# klt-j4k-ov2732.net
KiCad netlist of a schematic drawn in Altium Designer
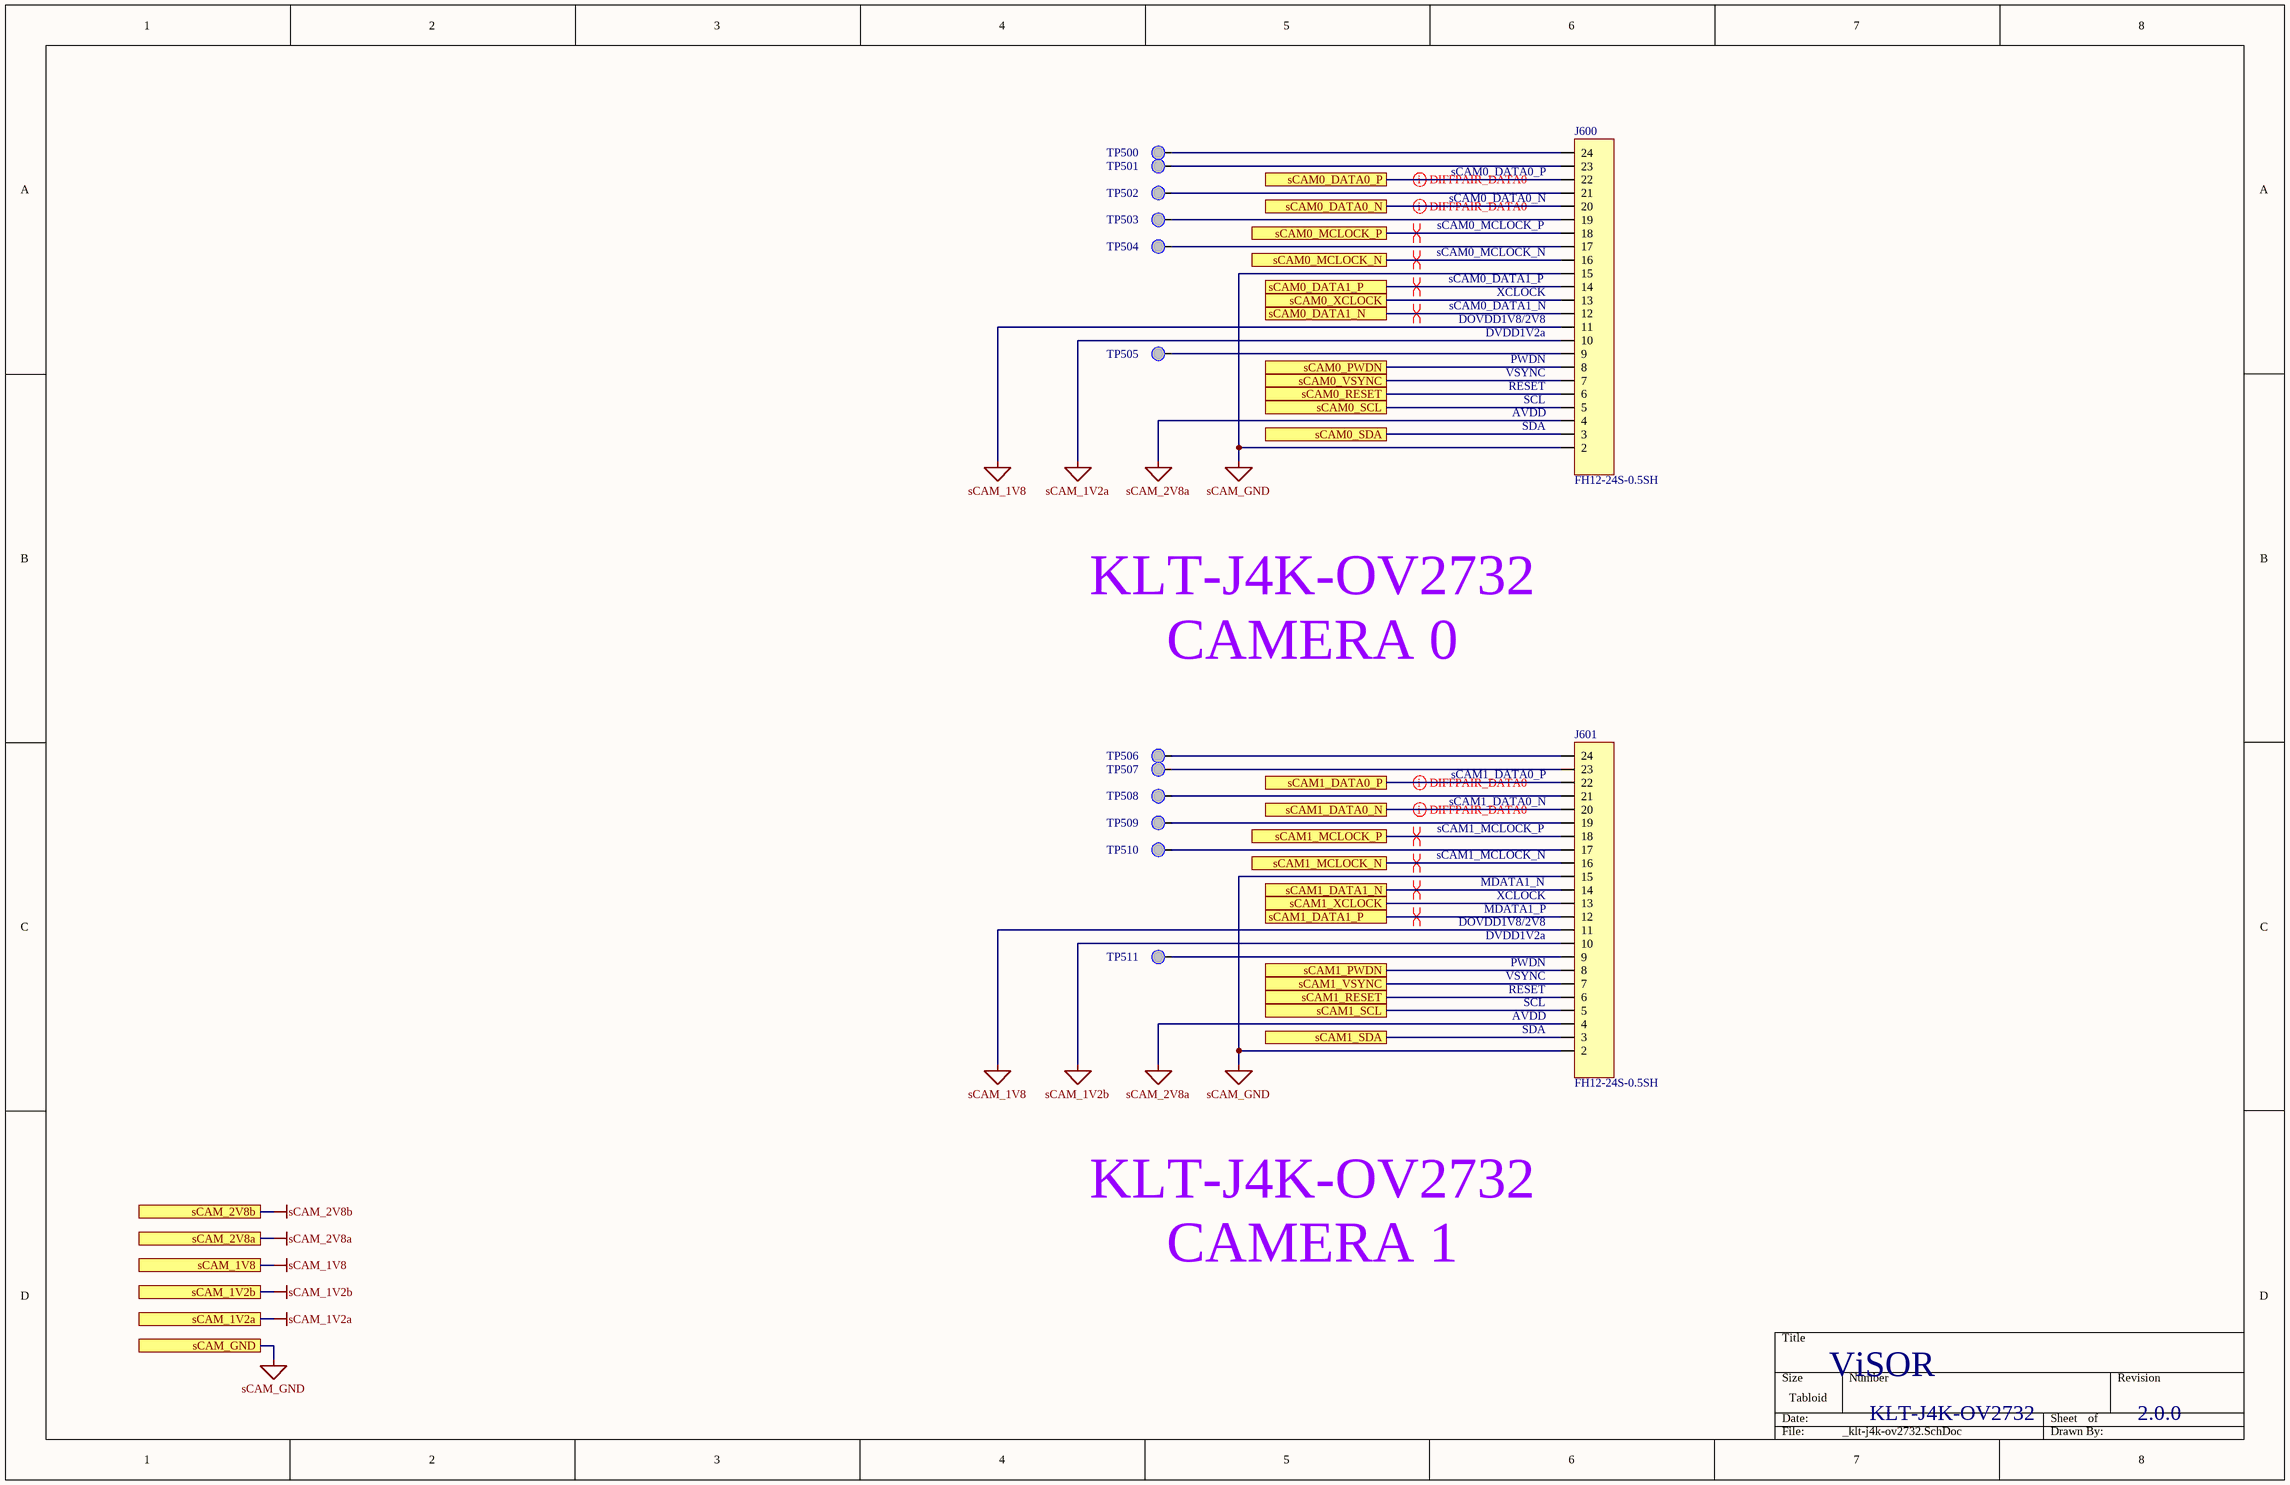
[diagram p0: _klt-j4k-ov2732.SchDoc]

(export (version "E")
  (design (tool "Eeschema 10.0.6"))
  (components
    (comp (ref "J600")
      (value "FH12-24S-0.5SH")
      (footprint "FH12-24S-0.5SH")
      (description "ONN FFC BOTTOM 24POS 0.50MM R/A")
      (libsource (lib "hirose") (part "FH12-24S-0.5SH"))
    )
    (comp (ref "J601")
      (value "FH12-24S-0.5SH")
      (footprint "FH12-24S-0.5SH")
      (description "ONN FFC BOTTOM 24POS 0.50MM R/A")
      (libsource (lib "hirose") (part "FH12-24S-0.5SH"))
    )
    (comp (ref "TP500") (value "TP") (footprint "TP_TH") (libsource (lib "common") (part "TP")))
    (comp (ref "TP501") (value "TP") (footprint "TP_TH") (libsource (lib "common") (part "TP")))
    (comp (ref "TP502") (value "TP") (footprint "TP_TH") (libsource (lib "common") (part "TP")))
    (comp (ref "TP503") (value "TP") (footprint "TP_TH") (libsource (lib "common") (part "TP")))
    (comp (ref "TP504") (value "TP") (footprint "TP_TH") (libsource (lib "common") (part "TP")))
    (comp (ref "TP505") (value "TP") (footprint "TP_TH") (libsource (lib "common") (part "TP")))
    (comp (ref "TP506") (value "TP") (footprint "TP_TH") (libsource (lib "common") (part "TP")))
    (comp (ref "TP507") (value "TP") (footprint "TP_TH") (libsource (lib "common") (part "TP")))
    (comp (ref "TP508") (value "TP") (footprint "TP_TH") (libsource (lib "common") (part "TP")))
    (comp (ref "TP509") (value "TP") (footprint "TP_TH") (libsource (lib "common") (part "TP")))
    (comp (ref "TP510") (value "TP") (footprint "TP_TH") (libsource (lib "common") (part "TP")))
    (comp (ref "TP511") (value "TP") (footprint "TP_TH") (libsource (lib "common") (part "TP")))
  )
  (nets
    (net (code "1") (name "/sCAM0_DATA0_N") (class "Default")
      (node (ref "J600") (pin "20") (pinfunction "20_20") (pintype "passive"))
    )
    (net (code "2") (name "/sCAM0_DATA0_P") (class "Default")
      (node (ref "J600") (pin "22") (pinfunction "22_22") (pintype "passive"))
    )
    (net (code "3") (name "/sCAM0_DATA1_N") (class "Default")
      (node (ref "J600") (pin "12") (pinfunction "12_12") (pintype "passive"))
    )
    (net (code "4") (name "/sCAM0_DATA1_P") (class "Default")
      (node (ref "J600") (pin "14") (pinfunction "14_14") (pintype "passive"))
    )
    (net (code "5") (name "/sCAM0_MCLOCK_N") (class "Default")
      (node (ref "J600") (pin "16") (pinfunction "16_16") (pintype "passive"))
    )
    (net (code "6") (name "/sCAM0_MCLOCK_P") (class "Default")
      (node (ref "J600") (pin "18") (pinfunction "18_18") (pintype "passive"))
    )
    (net (code "7") (name "/sCAM0_PWDN") (class "Default")
      (node (ref "J600") (pin "8") (pinfunction "8_8") (pintype "passive"))
    )
    (net (code "8") (name "/sCAM0_RESET") (class "Default")
      (node (ref "J600") (pin "6") (pinfunction "6_6") (pintype "passive"))
    )
    (net (code "9") (name "/sCAM0_SCL") (class "Default")
      (node (ref "J600") (pin "5") (pinfunction "5_5") (pintype "passive"))
    )
    (net (code "10") (name "/sCAM0_SDA") (class "Default")
      (node (ref "J600") (pin "3") (pinfunction "3_3") (pintype "passive"))
    )
    (net (code "11") (name "/sCAM0_VSYNC") (class "Default")
      (node (ref "J600") (pin "7") (pinfunction "7_7") (pintype "passive"))
    )
    (net (code "12") (name "/sCAM0_XCLOCK") (class "Default")
      (node (ref "J600") (pin "13") (pinfunction "13_13") (pintype "passive"))
    )
    (net (code "13") (name "/sCAM1_DATA0_N") (class "Default")
      (node (ref "J601") (pin "20") (pinfunction "20_20") (pintype "passive"))
    )
    (net (code "14") (name "/sCAM1_DATA0_P") (class "Default")
      (node (ref "J601") (pin "22") (pinfunction "22_22") (pintype "passive"))
    )
    (net (code "15") (name "/sCAM1_DATA1_N") (class "Default")
      (node (ref "J601") (pin "14") (pinfunction "14_14") (pintype "passive"))
    )
    (net (code "16") (name "/sCAM1_DATA1_P") (class "Default")
      (node (ref "J601") (pin "12") (pinfunction "12_12") (pintype "passive"))
    )
    (net (code "17") (name "/sCAM1_MCLOCK_N") (class "Default")
      (node (ref "J601") (pin "16") (pinfunction "16_16") (pintype "passive"))
    )
    (net (code "18") (name "/sCAM1_MCLOCK_P") (class "Default")
      (node (ref "J601") (pin "18") (pinfunction "18_18") (pintype "passive"))
    )
    (net (code "19") (name "/sCAM1_PWDN") (class "Default")
      (node (ref "J601") (pin "8") (pinfunction "8_8") (pintype "passive"))
    )
    (net (code "20") (name "/sCAM1_RESET") (class "Default")
      (node (ref "J601") (pin "6") (pinfunction "6_6") (pintype "passive"))
    )
    (net (code "21") (name "/sCAM1_SCL") (class "Default")
      (node (ref "J601") (pin "5") (pinfunction "5_5") (pintype "passive"))
    )
    (net (code "22") (name "/sCAM1_SDA") (class "Default")
      (node (ref "J601") (pin "3") (pinfunction "3_3") (pintype "passive"))
    )
    (net (code "23") (name "/sCAM1_VSYNC") (class "Default")
      (node (ref "J601") (pin "7") (pinfunction "7_7") (pintype "passive"))
    )
    (net (code "24") (name "/sCAM1_XCLOCK") (class "Default")
      (node (ref "J601") (pin "13") (pinfunction "13_13") (pintype "passive"))
    )
    (net (code "25") (name "Net-(J600-Pad9)") (class "Default")
      (node (ref "J600") (pin "9") (pinfunction "9_9") (pintype "passive"))
      (node (ref "TP505") (pin "1") (pinfunction "1_1") (pintype "passive"))
    )
    (net (code "26") (name "Net-(J600-Pad17)") (class "Default")
      (node (ref "J600") (pin "17") (pinfunction "17_17") (pintype "passive"))
      (node (ref "TP504") (pin "1") (pinfunction "1_1") (pintype "passive"))
    )
    (net (code "27") (name "Net-(J600-Pad19)") (class "Default")
      (node (ref "J600") (pin "19") (pinfunction "19_19") (pintype "passive"))
      (node (ref "TP503") (pin "1") (pinfunction "1_1") (pintype "passive"))
    )
    (net (code "28") (name "Net-(J600-Pad21)") (class "Default")
      (node (ref "J600") (pin "21") (pinfunction "21_21") (pintype "passive"))
      (node (ref "TP502") (pin "1") (pinfunction "1_1") (pintype "passive"))
    )
    (net (code "29") (name "Net-(J600-Pad23)") (class "Default")
      (node (ref "J600") (pin "23") (pinfunction "23_23") (pintype "passive"))
      (node (ref "TP501") (pin "1") (pinfunction "1_1") (pintype "passive"))
    )
    (net (code "30") (name "Net-(J600-Pad24)") (class "Default")
      (node (ref "J600") (pin "24") (pinfunction "24_24") (pintype "passive"))
      (node (ref "TP500") (pin "1") (pinfunction "1_1") (pintype "passive"))
    )
    (net (code "31") (name "Net-(J601-Pad9)") (class "Default")
      (node (ref "J601") (pin "9") (pinfunction "9_9") (pintype "passive"))
      (node (ref "TP511") (pin "1") (pinfunction "1_1") (pintype "passive"))
    )
    (net (code "32") (name "Net-(J601-Pad17)") (class "Default")
      (node (ref "J601") (pin "17") (pinfunction "17_17") (pintype "passive"))
      (node (ref "TP510") (pin "1") (pinfunction "1_1") (pintype "passive"))
    )
    (net (code "33") (name "Net-(J601-Pad19)") (class "Default")
      (node (ref "J601") (pin "19") (pinfunction "19_19") (pintype "passive"))
      (node (ref "TP509") (pin "1") (pinfunction "1_1") (pintype "passive"))
    )
    (net (code "34") (name "Net-(J601-Pad21)") (class "Default")
      (node (ref "J601") (pin "21") (pinfunction "21_21") (pintype "passive"))
      (node (ref "TP508") (pin "1") (pinfunction "1_1") (pintype "passive"))
    )
    (net (code "35") (name "Net-(J601-Pad23)") (class "Default")
      (node (ref "J601") (pin "23") (pinfunction "23_23") (pintype "passive"))
      (node (ref "TP507") (pin "1") (pinfunction "1_1") (pintype "passive"))
    )
    (net (code "36") (name "Net-(J601-Pad24)") (class "Default")
      (node (ref "J601") (pin "24") (pinfunction "24_24") (pintype "passive"))
      (node (ref "TP506") (pin "1") (pinfunction "1_1") (pintype "passive"))
    )
    (net (code "37") (name "sCAM_1V2a") (class "Default")
      (node (ref "J600") (pin "10") (pinfunction "10_10") (pintype "passive"))
    )
    (net (code "38") (name "sCAM_1V2b") (class "Default")
      (node (ref "J601") (pin "10") (pinfunction "10_10") (pintype "passive"))
    )
    (net (code "39") (name "sCAM_1V8") (class "Default")
      (node (ref "J600") (pin "11") (pinfunction "11_11") (pintype "passive"))
      (node (ref "J601") (pin "11") (pinfunction "11_11") (pintype "passive"))
    )
    (net (code "40") (name "sCAM_2V8a") (class "Default")
      (node (ref "J600") (pin "4") (pinfunction "4_4") (pintype "passive"))
      (node (ref "J601") (pin "4") (pinfunction "4_4") (pintype "passive"))
    )
    (net (code "42") (name "sCAM_GND") (class "Default")
      (node (ref "J600") (pin "15") (pinfunction "15_15") (pintype "passive"))
      (node (ref "J600") (pin "2") (pinfunction "2_2") (pintype "passive"))
      (node (ref "J601") (pin "15") (pinfunction "15_15") (pintype "passive"))
      (node (ref "J601") (pin "2") (pinfunction "2_2") (pintype "passive"))
    )
    (net (code "43") (name "unconnected-(J600-Pad1)") (class "Default")
      (node (ref "J600") (pin "1") (pinfunction "1_1") (pintype "passive"))
    )
    (net (code "44") (name "unconnected-(J601-Pad1)") (class "Default")
      (node (ref "J601") (pin "1") (pinfunction "1_1") (pintype "passive"))
    )
  )
)
